# Power_Board_Clone.net
KiCad netlist of a schematic drawn in Altium Designer
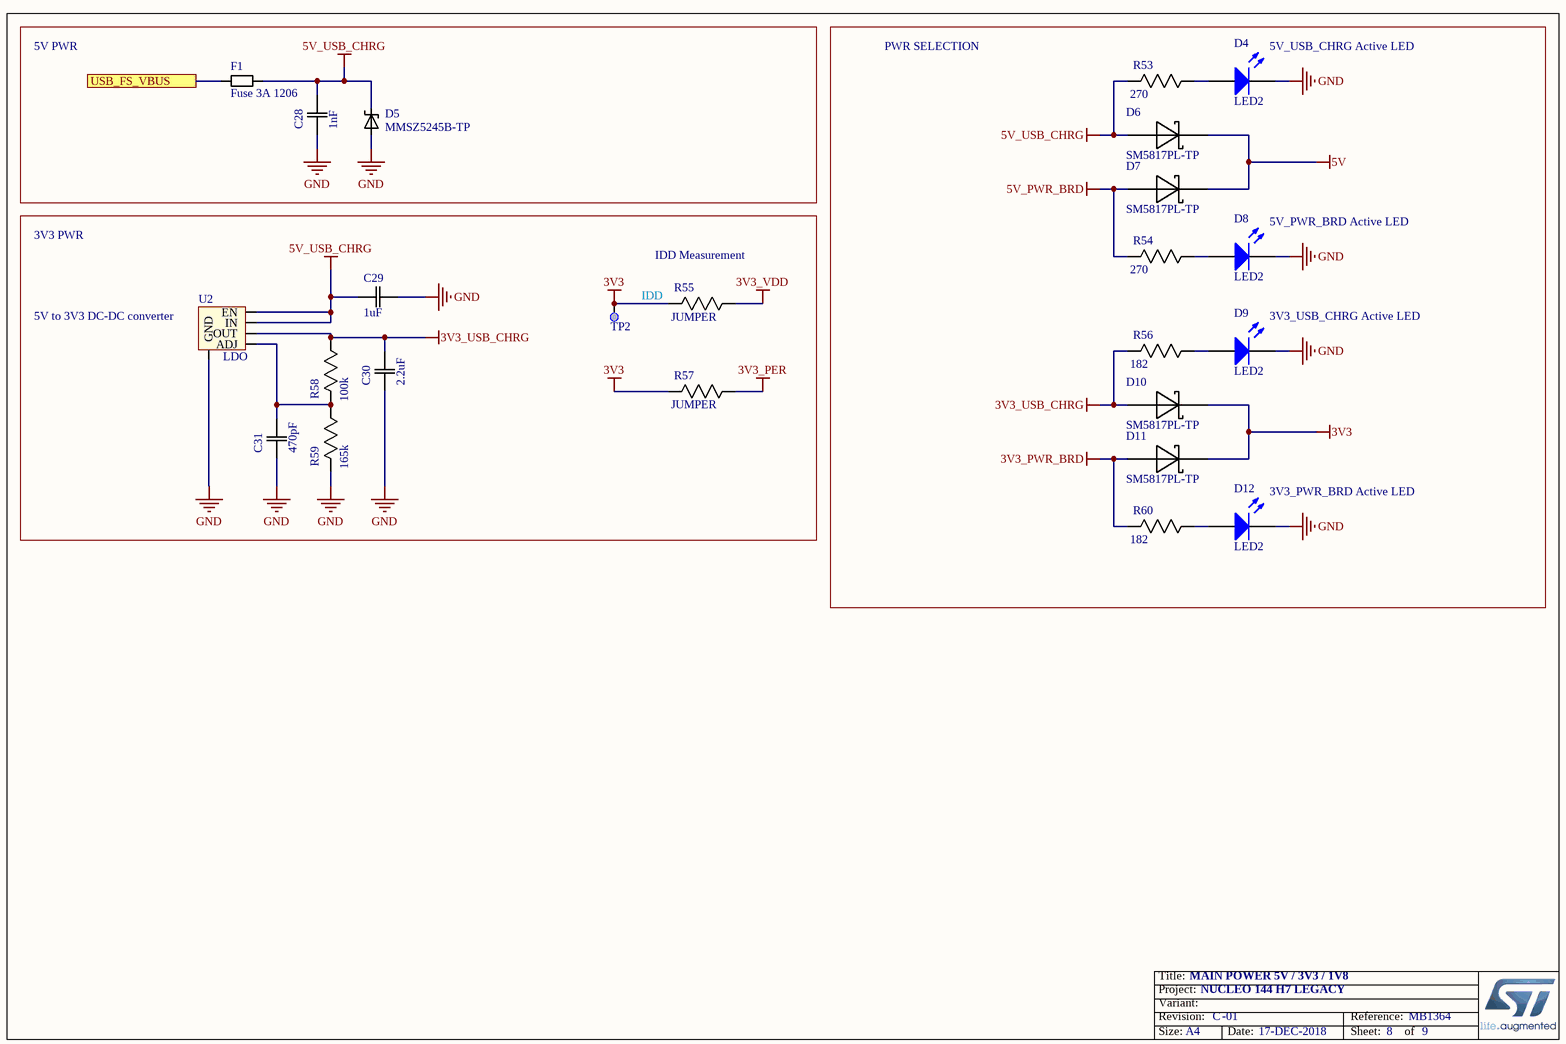
[diagram p0: Power_Board_Clone.SchDoc]

(export (version "E")
  (design (tool "Eeschema 10.0.6"))
  (components
    (comp (ref "C28")
      (value "1nF")
      (footprint "0805")
      (description "CAP CER 1000PF 50V X7R 0805")
      (fields (field (name "MP") "CC0805KRX7R9BB102") (field (name "MF") "Yageo"))
      (libsource (lib "AltiumLibraries") (part "CAP 1nF 0805"))
    )
    (comp (ref "C29")
      (value "1uF")
      (footprint "0805")
      (description "CAP CER 1UF 50V X7R 0805")
      (fields (field (name "MP") "CL21B105KBFNNNE") (field (name "MF") "Samsung Electro-Mechanics"))
      (libsource (lib "AltiumLibraries") (part "CAP 1uF 0805"))
    )
    (comp (ref "C30")
      (value "2.2uF")
      (footprint "0805")
      (description "CAP CER 1UF 50V X7R 0805")
      (fields (field (name "MP") "C0805C225K4RACTU") (field (name "MF") "KEMET"))
      (libsource (lib "AltiumLibraries") (part "CAP 2.2uF 0805"))
    )
    (comp (ref "C31")
      (value "470pF")
      (footprint "0805")
      (description "CAP CER 470PF 50V C0G/NPO 0805")
      (fields (field (name "MP") "CC0805JRNPO9BN471") (field (name "MF") "Yageo"))
      (libsource (lib "AltiumLibraries") (part "CAP 470pF 0805"))
    )
    (comp (ref "D4")
      (value "LED2")
      (footprint "3.2X1.6X1.1")
      (description "Typical RED, GREEN, YELLOW, AMBER GaAs LED")
      (fields (field (name "MF") "Lite-On Inc.") (field (name "MP") "LTST-C191KGKT"))
      (libsource (lib "AltiumLibraries") (part "LED GREEN SMD"))
    )
    (comp (ref "D5")
      (value "MMSZ5245B-TP")
      (footprint "SOD-123")
      (description "Zener Diode 15V 500mW ±5% Surface Mount SOD-123")
      (fields (field (name "MP") "MMSZ5224BT1G") (field (name "MF") "ON Semiconductor"))
      (libsource (lib "AltiumLibraries") (part "MMSZ5245B-TP"))
    )
    (comp (ref "D6")
      (value "SM5817PL-TP")
      (footprint "SOD-123")
      (description "Diode Schottky 20V 1A Surface Mount SOD-123FL")
      (fields (field (name "MF") "Micro Commercial Co"))
      (libsource (lib "AltiumLibraries") (part "SM5817PL-TP"))
    )
    (comp (ref "D7")
      (value "SM5817PL-TP")
      (footprint "SOD-123")
      (description "Diode Schottky 20V 1A Surface Mount SOD-123FL")
      (fields (field (name "MF") "Micro Commercial Co"))
      (libsource (lib "AltiumLibraries") (part "SM5817PL-TP"))
    )
    (comp (ref "D8")
      (value "LED2")
      (footprint "3.2X1.6X1.1")
      (description "Typical RED, GREEN, YELLOW, AMBER GaAs LED")
      (fields (field (name "MF") "Lite-On Inc.") (field (name "MP") "LTST-C191KGKT"))
      (libsource (lib "AltiumLibraries") (part "LED GREEN SMD"))
    )
    (comp (ref "D9")
      (value "LED2")
      (footprint "3.2X1.6X1.1")
      (description "Typical RED, GREEN, YELLOW, AMBER GaAs LED")
      (fields (field (name "MF") "Lite-On Inc.") (field (name "MP") "LTST-C191KGKT"))
      (libsource (lib "AltiumLibraries") (part "LED GREEN SMD"))
    )
    (comp (ref "D10")
      (value "SM5817PL-TP")
      (footprint "SOD-123")
      (description "Diode Schottky 20V 1A Surface Mount SOD-123FL")
      (fields (field (name "MF") "Micro Commercial Co"))
      (libsource (lib "AltiumLibraries") (part "SM5817PL-TP"))
    )
    (comp (ref "D11")
      (value "SM5817PL-TP")
      (footprint "SOD-123")
      (description "Diode Schottky 20V 1A Surface Mount SOD-123FL")
      (fields (field (name "MF") "Micro Commercial Co"))
      (libsource (lib "AltiumLibraries") (part "SM5817PL-TP"))
    )
    (comp (ref "D12")
      (value "LED2")
      (footprint "3.2X1.6X1.1")
      (description "Typical RED, GREEN, YELLOW, AMBER GaAs LED")
      (fields (field (name "MF") "Lite-On Inc.") (field (name "MP") "LTST-C191KGKT"))
      (libsource (lib "AltiumLibraries") (part "LED GREEN SMD"))
    )
    (comp (ref "F1")
      (value "Fuse 3A 1206")
      (footprint "1206")
      (description "FUSE 3.0A 63VAC/DC SLOW 1206")
      (fields (field (name "MF") "Bel Fuse Inc.") (field (name "MP") "0685T3000-01"))
      (libsource (lib "AltiumLibraries") (part "Fuse 3A 1206"))
    )
    (comp (ref "R53")
      (value "270")
      (footprint "0805")
      (description "RES SMD 270 OHM 5% 1/8W 0805")
      (fields (field (name "MP") "RC0805JR-07270RL") (field (name "MF") "Yageo"))
      (libsource (lib "AltiumLibraries") (part "RES 270 0805"))
    )
    (comp (ref "R54")
      (value "270")
      (footprint "0805")
      (description "RES SMD 270 OHM 5% 1/8W 0805")
      (fields (field (name "MP") "RC0805JR-07270RL") (field (name "MF") "Yageo"))
      (libsource (lib "AltiumLibraries") (part "RES 270 0805"))
    )
    (comp (ref "R55")
      (value "JUMPER")
      (footprint "0805")
      (description "RES SMD 0 OHM JUMPER 1/8W 0805")
      (fields (field (name "MP") "RC0805JR-070RL") (field (name "MF") "Yageo"))
      (libsource (lib "AltiumLibraries") (part "RES 0 0805"))
    )
    (comp (ref "R56")
      (value "182")
      (footprint "0805")
      (description "RES SMD 182 OHM 1% 1/8W 0805")
      (fields (field (name "MP") "ERJ-6ENF1820V") (field (name "MF") "Panasonic Electronic Components"))
      (libsource (lib "AltiumLibraries") (part "RES 182 0805"))
    )
    (comp (ref "R57")
      (value "JUMPER")
      (footprint "0805")
      (description "RES SMD 0 OHM JUMPER 1/8W 0805")
      (fields (field (name "MP") "RC0805JR-070RL") (field (name "MF") "Yageo"))
      (libsource (lib "AltiumLibraries") (part "RES 0 0805"))
    )
    (comp (ref "R58")
      (value "100k")
      (footprint "0805")
      (description "RES SMD 100K OHM 1% 1/8W 0805")
      (fields (field (name "MP") "RC0805FR-07100KL") (field (name "MF") "Yageo"))
      (libsource (lib "AltiumLibraries") (part "RES 100k 0805"))
    )
    (comp (ref "R59")
      (value "165k")
      (footprint "0805")
      (fields (field (name "MP") "RK73H2ATTD1653F") (field (name "MF") "KOA Speer Electronics, Inc."))
      (libsource (lib "AltiumLibraries") (part "RES 165k 0805"))
    )
    (comp (ref "R60")
      (value "182")
      (footprint "0805")
      (description "RES SMD 182 OHM 1% 1/8W 0805")
      (fields (field (name "MP") "ERJ-6ENF1820V") (field (name "MF") "Panasonic Electronic Components"))
      (libsource (lib "AltiumLibraries") (part "RES 182 0805"))
    )
    (comp (ref "TP2")
      (value "Test Point")
      (footprint "TP_SMD_1MM")
      (description "Test Point 1mm")
      (fields (field (name "INTERNAL_PART_NUMBER") "MCD-00074") (field (name "MANUFACTURER") "n/a"))
      (libsource (lib "MCD_PARTS_database") (part "Test Point"))
    )
    (comp (ref "U2")
      (value "LDO")
      (footprint "REG LIN POS ADJ 500MA 8SOIC")
      (description "Linear Voltage Regulator IC  1 Output  500mA 8-SOIC")
      (fields (field (name "MF") "Texas Instruments") (field (name "MP") "TL5209DR"))
      (libsource (lib "AltiumLibraries") (part "REG LIN POS ADJ"))
    )
  )
  (nets
    (net (code "1") (name "/USB_FS_VBUS") (class "Default")
      (node (ref "F1") (pin "1") (pinfunction "1_1") (pintype "passive"))
    )
    (net (code "2") (name "3V3") (class "Default")
      (node (ref "D10") (pin "C") (pinfunction "K_C") (pintype "passive"))
      (node (ref "D11") (pin "C") (pinfunction "K_C") (pintype "passive"))
      (node (ref "R55") (pin "2") (pinfunction "R2_2") (pintype "passive"))
      (node (ref "R57") (pin "2") (pinfunction "R2_2") (pintype "passive"))
      (node (ref "TP2") (pin "1") (pinfunction "1_1") (pintype "passive"))
    )
    (net (code "3") (name "3V3_PER") (class "Default")
      (node (ref "R57") (pin "1") (pinfunction "R1_1") (pintype "passive"))
    )
    (net (code "4") (name "3V3_PWR_BRD") (class "Default")
      (node (ref "D11") (pin "A") (pinfunction "A_A") (pintype "passive"))
      (node (ref "R60") (pin "2") (pinfunction "R2_2") (pintype "passive"))
    )
    (net (code "5") (name "3V3_USB_CHRG") (class "Default")
      (node (ref "C30") (pin "2") (pinfunction "C2_2") (pintype "passive"))
      (node (ref "D10") (pin "A") (pinfunction "A_A") (pintype "passive"))
      (node (ref "R56") (pin "2") (pinfunction "R2_2") (pintype "passive"))
      (node (ref "R58") (pin "1") (pinfunction "R1_1") (pintype "passive"))
      (node (ref "U2") (pin "OUT") (pinfunction "OUT_OUT") (pintype "passive"))
    )
    (net (code "6") (name "3V3_VDD") (class "Default")
      (node (ref "R55") (pin "1") (pinfunction "R1_1") (pintype "passive"))
    )
    (net (code "7") (name "5V") (class "Default")
      (node (ref "D6") (pin "C") (pinfunction "K_C") (pintype "passive"))
      (node (ref "D7") (pin "C") (pinfunction "K_C") (pintype "passive"))
    )
    (net (code "8") (name "5V_PWR_BRD") (class "Default")
      (node (ref "D7") (pin "A") (pinfunction "A_A") (pintype "passive"))
      (node (ref "R54") (pin "2") (pinfunction "R2_2") (pintype "passive"))
    )
    (net (code "9") (name "5V_USB_CHRG") (class "Default")
      (node (ref "C28") (pin "2") (pinfunction "C2_2") (pintype "passive"))
      (node (ref "C29") (pin "1") (pinfunction "C1_1") (pintype "passive"))
      (node (ref "D5") (pin "C") (pinfunction "C_C") (pintype "passive"))
      (node (ref "D6") (pin "A") (pinfunction "A_A") (pintype "passive"))
      (node (ref "F1") (pin "2") (pinfunction "2_2") (pintype "passive"))
      (node (ref "R53") (pin "2") (pinfunction "R2_2") (pintype "passive"))
      (node (ref "U2") (pin "EN") (pinfunction "EN_EN") (pintype "passive"))
      (node (ref "U2") (pin "IN") (pinfunction "IN_IN") (pintype "passive"))
    )
    (net (code "10") (name "GND") (class "Default")
      (node (ref "C28") (pin "1") (pinfunction "C1_1") (pintype "passive"))
      (node (ref "C29") (pin "2") (pinfunction "C2_2") (pintype "passive"))
      (node (ref "C30") (pin "1") (pinfunction "C1_1") (pintype "passive"))
      (node (ref "C31") (pin "1") (pinfunction "C1_1") (pintype "passive"))
      (node (ref "D12") (pin "2") (pinfunction "K_2") (pintype "passive"))
      (node (ref "D4") (pin "2") (pinfunction "K_2") (pintype "passive"))
      (node (ref "D5") (pin "A") (pinfunction "A_A") (pintype "passive"))
      (node (ref "D8") (pin "2") (pinfunction "K_2") (pintype "passive"))
      (node (ref "D9") (pin "2") (pinfunction "K_2") (pintype "passive"))
      (node (ref "R59") (pin "2") (pinfunction "R2_2") (pintype "passive"))
      (node (ref "U2") (pin "GND") (pinfunction "GND_GND") (pintype "passive"))
    )
    (net (code "11") (name "Net-(C31-C2)") (class "Default")
      (node (ref "C31") (pin "2") (pinfunction "C2_2") (pintype "passive"))
      (node (ref "R58") (pin "2") (pinfunction "R2_2") (pintype "passive"))
      (node (ref "R59") (pin "1") (pinfunction "R1_1") (pintype "passive"))
      (node (ref "U2") (pin "ADJ") (pinfunction "ADJ_ADJ") (pintype "passive"))
    )
    (net (code "12") (name "Net-(D4-A)") (class "Default")
      (node (ref "D4") (pin "1") (pinfunction "A_1") (pintype "passive"))
      (node (ref "R53") (pin "1") (pinfunction "R1_1") (pintype "passive"))
    )
    (net (code "13") (name "Net-(D8-A)") (class "Default")
      (node (ref "D8") (pin "1") (pinfunction "A_1") (pintype "passive"))
      (node (ref "R54") (pin "1") (pinfunction "R1_1") (pintype "passive"))
    )
    (net (code "14") (name "Net-(D9-A)") (class "Default")
      (node (ref "D9") (pin "1") (pinfunction "A_1") (pintype "passive"))
      (node (ref "R56") (pin "1") (pinfunction "R1_1") (pintype "passive"))
    )
    (net (code "15") (name "Net-(D12-A)") (class "Default")
      (node (ref "D12") (pin "1") (pinfunction "A_1") (pintype "passive"))
      (node (ref "R60") (pin "1") (pinfunction "R1_1") (pintype "passive"))
    )
  )
)
